# 2_66.net
KiCad netlist of a schematic drawn in EasyEDA Pro
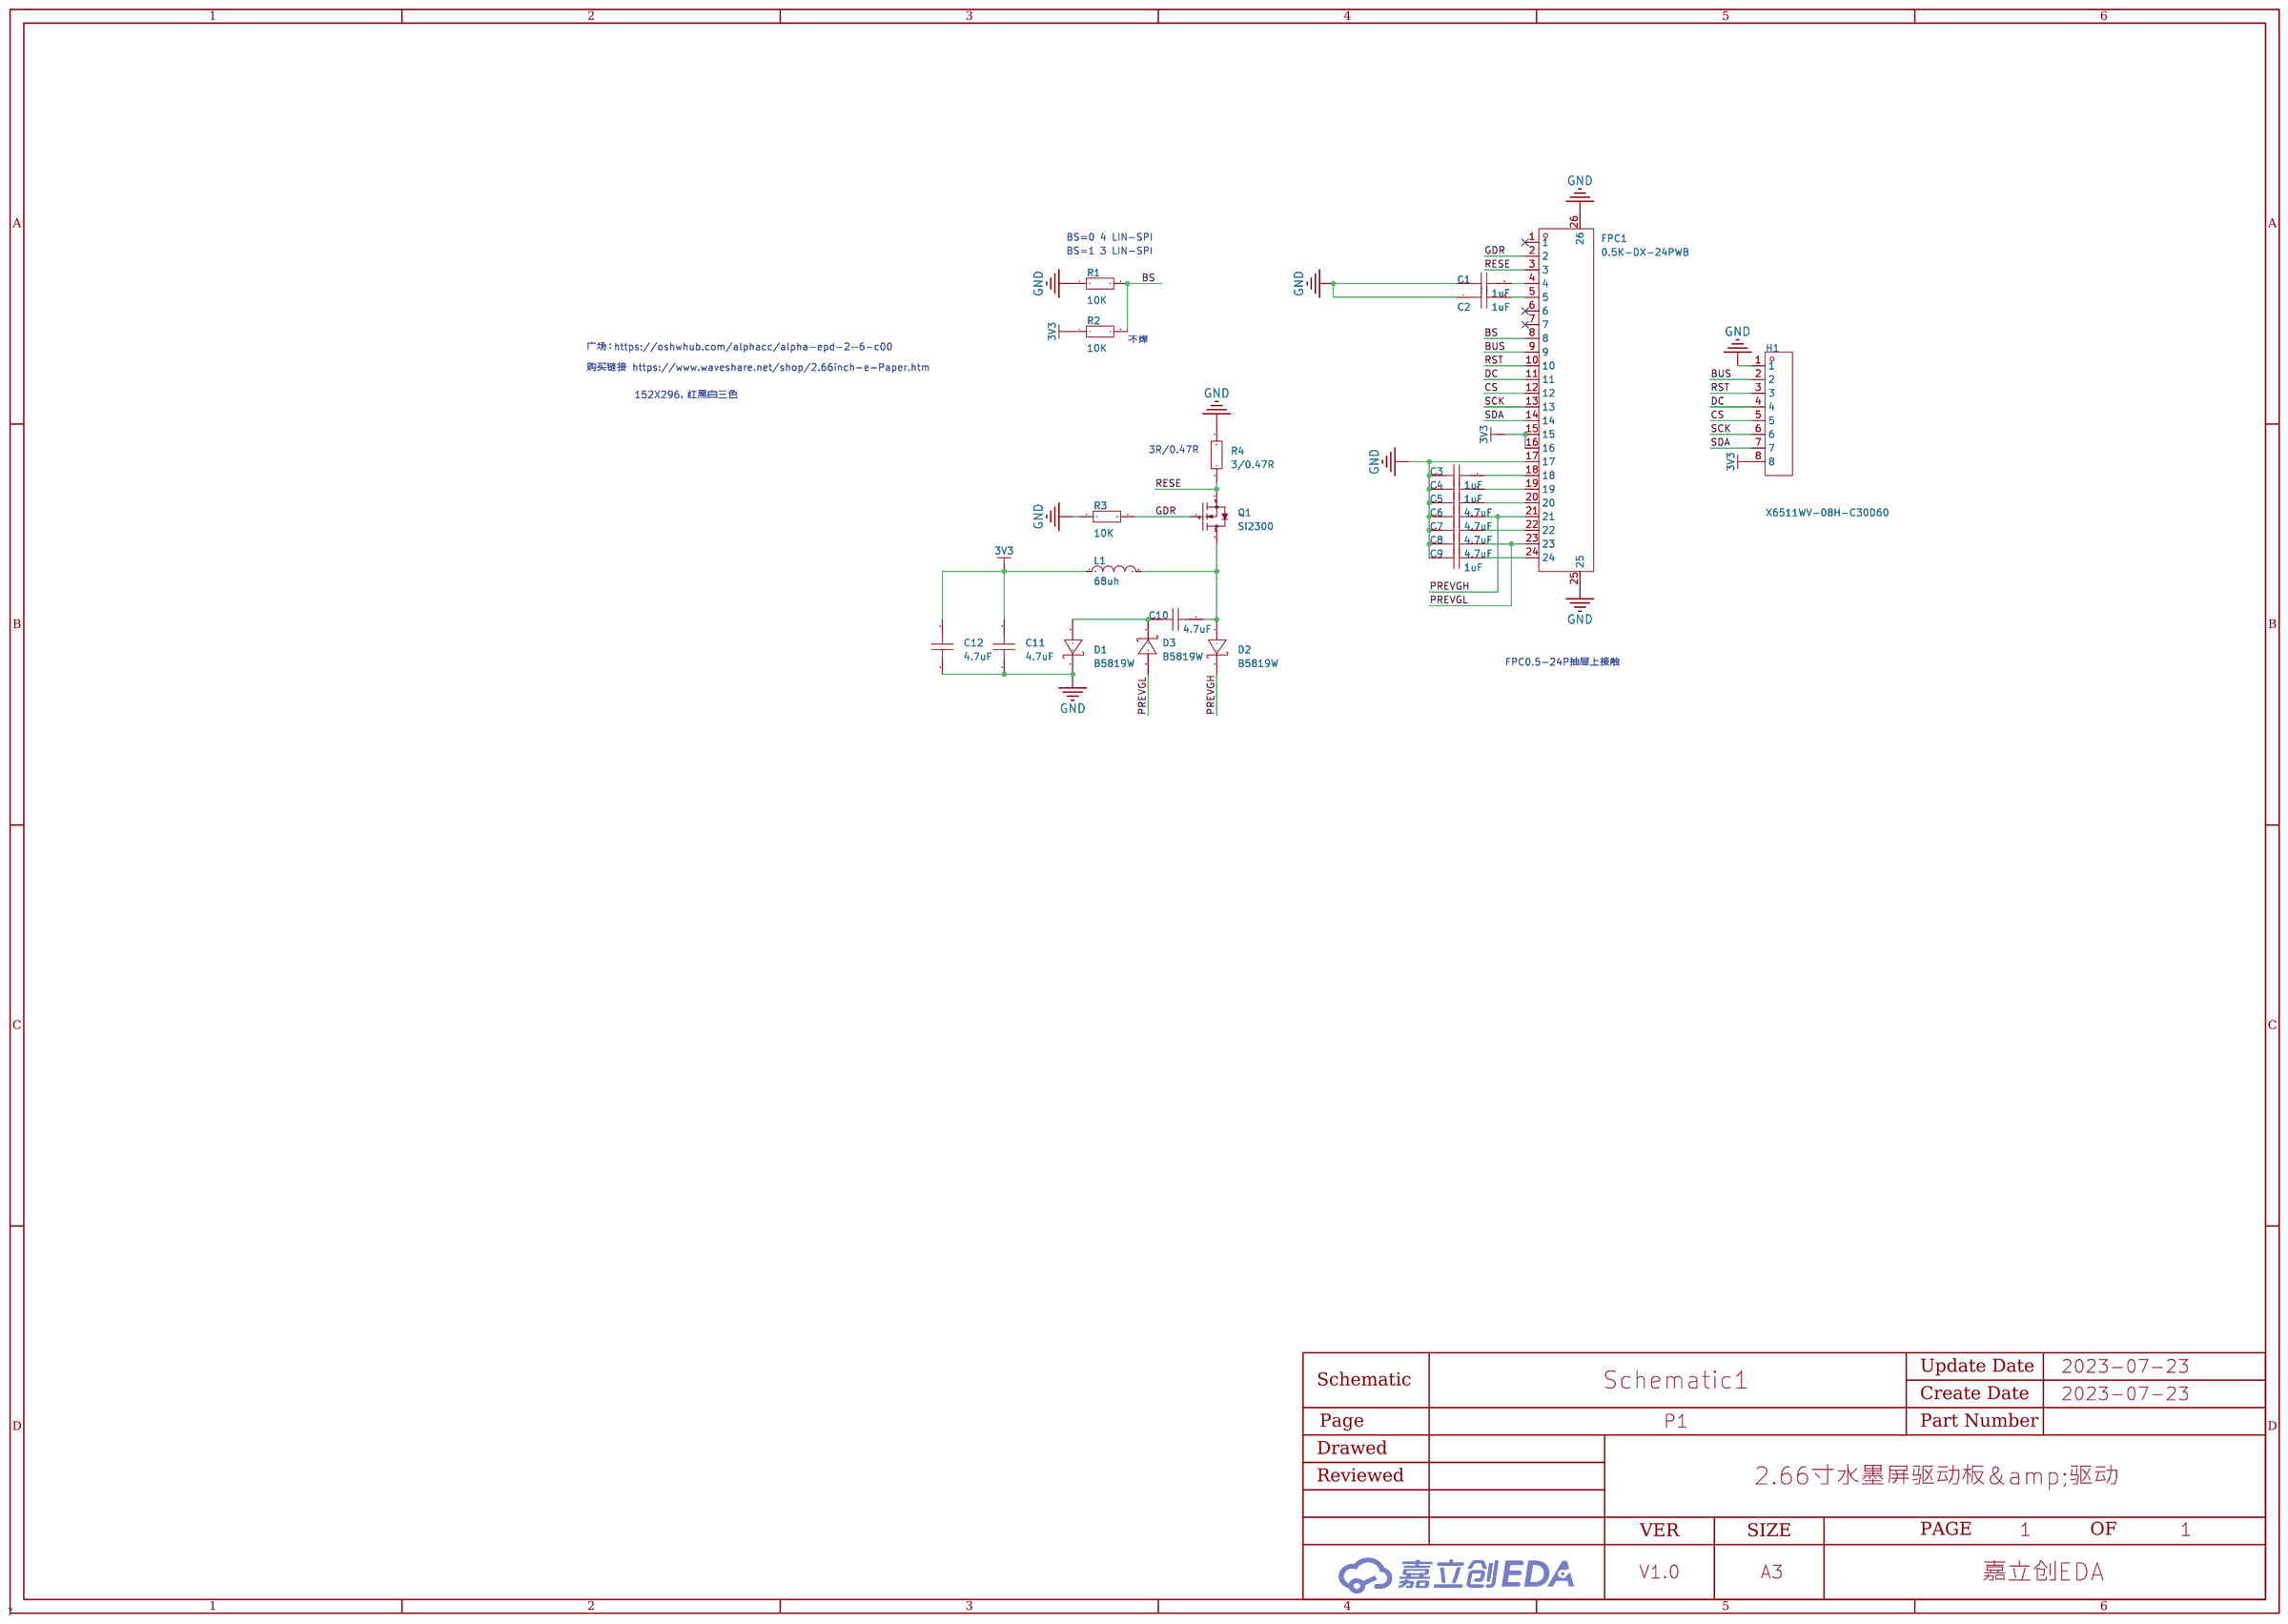
[diagram p0: schematic sheet]

(export (version "E")
  (design (tool "Eeschema 10.0.6"))
  (components
    (comp (ref "C1")
      (value "1uF")
      (footprint "easyedapro:C0603")
      (libsource (lib "easyedapro") (part "CapAcitance"))
    )
    (comp (ref "C2")
      (value "1uF")
      (footprint "easyedapro:C0603")
      (libsource (lib "easyedapro") (part "CapAcitance"))
    )
    (comp (ref "C3")
      (value "1uF")
      (footprint "easyedapro:C0603")
      (libsource (lib "easyedapro") (part "CapAcitance"))
    )
    (comp (ref "C4")
      (value "1uF")
      (footprint "easyedapro:C0603")
      (libsource (lib "easyedapro") (part "CapAcitance"))
    )
    (comp (ref "C5")
      (value "4.7uF")
      (footprint "easyedapro:C0603")
      (libsource (lib "easyedapro") (part "CapAcitance"))
    )
    (comp (ref "C6")
      (value "4.7uF")
      (footprint "easyedapro:C0603")
      (libsource (lib "easyedapro") (part "CapAcitance"))
    )
    (comp (ref "C7")
      (value "4.7uF")
      (footprint "easyedapro:C0603")
      (libsource (lib "easyedapro") (part "CapAcitance"))
    )
    (comp (ref "C8")
      (value "4.7uF")
      (footprint "easyedapro:C0603")
      (libsource (lib "easyedapro") (part "CapAcitance"))
    )
    (comp (ref "C9")
      (value "1uF")
      (footprint "easyedapro:C0603")
      (libsource (lib "easyedapro") (part "CapAcitance"))
    )
    (comp (ref "C10")
      (value "4.7uF")
      (footprint "easyedapro:C0603")
      (libsource (lib "easyedapro") (part "CapAcitance"))
    )
    (comp (ref "C11")
      (value "4.7uF")
      (footprint "easyedapro:C0603")
      (libsource (lib "easyedapro") (part "CapAcitance"))
    )
    (comp (ref "C12")
      (value "4.7uF")
      (footprint "easyedapro:C0603")
      (libsource (lib "easyedapro") (part "CapAcitance"))
    )
    (comp (ref "D1")
      (value "B5819W")
      (footprint "easyedapro:SOD-123_L2.8-W1.8-LS3.7-RD")
      (description "直流反向耐压(Vr):40V;平均整流电流(Io):1A;正向压降(Vf):600mV@1A;")
      (fields (field (name "Manufacturer") "MDD"))
      (libsource (lib "easyedapro") (part "B5819W"))
    )
    (comp (ref "D2")
      (value "B5819W")
      (footprint "easyedapro:SOD-123_L2.8-W1.8-LS3.7-RD")
      (description "直流反向耐压(Vr):40V;平均整流电流(Io):1A;正向压降(Vf):600mV@1A;")
      (fields (field (name "Manufacturer") "MDD"))
      (libsource (lib "easyedapro") (part "B5819W"))
    )
    (comp (ref "D3")
      (value "B5819W")
      (footprint "easyedapro:SOD-123_L2.8-W1.8-LS3.7-RD")
      (description "直流反向耐压(Vr):40V;平均整流电流(Io):1A;正向压降(Vf):600mV@1A;")
      (fields (field (name "Manufacturer") "MDD"))
      (libsource (lib "easyedapro") (part "B5819W"))
    )
    (comp (ref "FPC1")
      (value "0.5K-DX-24PWB")
      (footprint "easyedapro:FPC-SMD_24P-P0.50_HDGC_0.5K-DX-24PWBG")
      (description "FPC0.5间距2.0高掀盖式下接24P")
      (fields (field (name "Manufacturer") "HDGC(华德共创)"))
      (libsource (lib "easyedapro") (part "0.5K-DX-24PWB"))
    )
    (comp (ref "H1")
      (value "X6511WV-08H-C30D60")
      (footprint "easyedapro:HDR-TH_8P-P2.54-V-M")
      (fields (field (name "Manufacturer") "XKB Connectivity(中国星坤)"))
      (libsource (lib "easyedapro") (part "X6511WV-08H-C30D60"))
    )
    (comp (ref "L1")
      (value "68uh")
      (footprint "easyedapro:IND-SMD_L4.5-W4.0")
      (fields (field (name "Manufacturer") "DMBJ(振宝佳)"))
      (libsource (lib "easyedapro") (part "CD43-2R2M"))
    )
    (comp (ref "Q1")
      (value "SI2300")
      (footprint "easyedapro:SOT-23-3_L2.9-W1.3-P1.90-LS2.4-BR")
      (fields (field (name "Manufacturer") "Hottech(合科泰)"))
      (libsource (lib "easyedapro") (part "SI2300"))
    )
    (comp (ref "R1") (value "10K") (footprint "easyedapro:R0603") (libsource (lib "easyedapro") (part "电阻")))
    (comp (ref "R2") (value "10K") (footprint "easyedapro:R0603") (libsource (lib "easyedapro") (part "电阻")))
    (comp (ref "R3") (value "10K") (footprint "easyedapro:R0603") (libsource (lib "easyedapro") (part "电阻")))
    (comp (ref "R4")
      (value "3/0.47R")
      (footprint "easyedapro:R0603")
      (libsource (lib "easyedapro") (part "电阻"))
    )
  )
  (nets
    (net (code "1") (name "/BS") (class "Default")
      (node (ref "FPC1") (pin "8") (pinfunction "8_8") (pintype "input"))
      (node (ref "R1") (pin "2") (pinfunction "2_2") (pintype "input"))
      (node (ref "R2") (pin "2") (pinfunction "2_2") (pintype "input"))
    )
    (net (code "2") (name "/BUS") (class "Default")
      (node (ref "FPC1") (pin "9") (pinfunction "9_9") (pintype "input"))
      (node (ref "H1") (pin "2") (pinfunction "2_2") (pintype "input"))
    )
    (net (code "3") (name "/CS") (class "Default")
      (node (ref "FPC1") (pin "12") (pinfunction "12_12") (pintype "input"))
      (node (ref "H1") (pin "5") (pinfunction "5_5") (pintype "input"))
    )
    (net (code "4") (name "/DC") (class "Default")
      (node (ref "FPC1") (pin "11") (pinfunction "11_11") (pintype "input"))
      (node (ref "H1") (pin "4") (pinfunction "4_4") (pintype "input"))
    )
    (net (code "5") (name "/GDR") (class "Default")
      (node (ref "FPC1") (pin "2") (pinfunction "2_2") (pintype "input"))
      (node (ref "Q1") (pin "1") (pinfunction "G_1") (pintype "input"))
      (node (ref "R3") (pin "2") (pinfunction "2_2") (pintype "input"))
    )
    (net (code "6") (name "/PREVGH") (class "Default")
      (node (ref "C6") (pin "2") (pinfunction "2_2") (pintype "input"))
      (node (ref "D2") (pin "1") (pinfunction "K_1") (pintype "input"))
      (node (ref "FPC1") (pin "21") (pinfunction "21_21") (pintype "input"))
    )
    (net (code "7") (name "/PREVGL") (class "Default")
      (node (ref "C8") (pin "2") (pinfunction "2_2") (pintype "input"))
      (node (ref "D3") (pin "2") (pinfunction "A_2") (pintype "input"))
      (node (ref "FPC1") (pin "23") (pinfunction "23_23") (pintype "input"))
    )
    (net (code "8") (name "/RESE") (class "Default")
      (node (ref "FPC1") (pin "3") (pinfunction "3_3") (pintype "input"))
      (node (ref "Q1") (pin "2") (pinfunction "S_2") (pintype "input"))
      (node (ref "R4") (pin "1") (pinfunction "1_1") (pintype "input"))
    )
    (net (code "9") (name "/RST") (class "Default")
      (node (ref "FPC1") (pin "10") (pinfunction "10_10") (pintype "input"))
      (node (ref "H1") (pin "3") (pinfunction "3_3") (pintype "input"))
    )
    (net (code "10") (name "/SCK") (class "Default")
      (node (ref "FPC1") (pin "13") (pinfunction "13_13") (pintype "input"))
      (node (ref "H1") (pin "6") (pinfunction "6_6") (pintype "input"))
    )
    (net (code "11") (name "/SDA") (class "Default")
      (node (ref "FPC1") (pin "14") (pinfunction "14_14") (pintype "input"))
      (node (ref "H1") (pin "7") (pinfunction "7_7") (pintype "input"))
    )
    (net (code "12") (name "3V3") (class "Default")
      (node (ref "C11") (pin "2") (pinfunction "2_2") (pintype "input"))
      (node (ref "C12") (pin "2") (pinfunction "2_2") (pintype "input"))
      (node (ref "FPC1") (pin "15") (pinfunction "15_15") (pintype "input"))
      (node (ref "FPC1") (pin "16") (pinfunction "16_16") (pintype "input"))
      (node (ref "H1") (pin "8") (pinfunction "8_8") (pintype "input"))
      (node (ref "L1") (pin "1") (pinfunction "1_1") (pintype "input"))
      (node (ref "R2") (pin "1") (pinfunction "1_1") (pintype "input"))
    )
    (net (code "13") (name "GND") (class "Default")
      (node (ref "C1") (pin "1") (pinfunction "1_1") (pintype "input"))
      (node (ref "C11") (pin "1") (pinfunction "1_1") (pintype "input"))
      (node (ref "C12") (pin "1") (pinfunction "1_1") (pintype "input"))
      (node (ref "C2") (pin "1") (pinfunction "1_1") (pintype "input"))
      (node (ref "C3") (pin "1") (pinfunction "1_1") (pintype "input"))
      (node (ref "C4") (pin "1") (pinfunction "1_1") (pintype "input"))
      (node (ref "C5") (pin "1") (pinfunction "1_1") (pintype "input"))
      (node (ref "C6") (pin "1") (pinfunction "1_1") (pintype "input"))
      (node (ref "C7") (pin "1") (pinfunction "1_1") (pintype "input"))
      (node (ref "C8") (pin "1") (pinfunction "1_1") (pintype "input"))
      (node (ref "C9") (pin "1") (pinfunction "1_1") (pintype "input"))
      (node (ref "D1") (pin "1") (pinfunction "K_1") (pintype "input"))
      (node (ref "FPC1") (pin "17") (pinfunction "17_17") (pintype "input"))
      (node (ref "FPC1") (pin "25") (pinfunction "25_25") (pintype "input"))
      (node (ref "FPC1") (pin "26") (pinfunction "26_26") (pintype "input"))
      (node (ref "H1") (pin "1") (pinfunction "1_1") (pintype "input"))
      (node (ref "R1") (pin "1") (pinfunction "1_1") (pintype "input"))
      (node (ref "R3") (pin "1") (pinfunction "1_1") (pintype "input"))
      (node (ref "R4") (pin "2") (pinfunction "2_2") (pintype "input"))
    )
    (net (code "14") (name "Net-(C1-Pad2)") (class "Default")
      (node (ref "C1") (pin "2") (pinfunction "2_2") (pintype "input"))
      (node (ref "FPC1") (pin "4") (pinfunction "4_4") (pintype "input"))
    )
    (net (code "15") (name "Net-(C2-Pad2)") (class "Default")
      (node (ref "C2") (pin "2") (pinfunction "2_2") (pintype "input"))
      (node (ref "FPC1") (pin "5") (pinfunction "5_5") (pintype "input"))
    )
    (net (code "16") (name "Net-(C3-Pad2)") (class "Default")
      (node (ref "C3") (pin "2") (pinfunction "2_2") (pintype "input"))
      (node (ref "FPC1") (pin "18") (pinfunction "18_18") (pintype "input"))
    )
    (net (code "17") (name "Net-(C4-Pad2)") (class "Default")
      (node (ref "C4") (pin "2") (pinfunction "2_2") (pintype "input"))
      (node (ref "FPC1") (pin "19") (pinfunction "19_19") (pintype "input"))
    )
    (net (code "18") (name "Net-(C5-Pad2)") (class "Default")
      (node (ref "C5") (pin "2") (pinfunction "2_2") (pintype "input"))
      (node (ref "FPC1") (pin "20") (pinfunction "20_20") (pintype "input"))
    )
    (net (code "19") (name "Net-(C7-Pad2)") (class "Default")
      (node (ref "C7") (pin "2") (pinfunction "2_2") (pintype "input"))
      (node (ref "FPC1") (pin "22") (pinfunction "22_22") (pintype "input"))
    )
    (net (code "20") (name "Net-(C9-Pad2)") (class "Default")
      (node (ref "C9") (pin "2") (pinfunction "2_2") (pintype "input"))
      (node (ref "FPC1") (pin "24") (pinfunction "24_24") (pintype "input"))
    )
    (net (code "21") (name "Net-(D1-A)") (class "Default")
      (node (ref "C10") (pin "1") (pinfunction "1_1") (pintype "input"))
      (node (ref "D1") (pin "2") (pinfunction "A_2") (pintype "input"))
      (node (ref "D3") (pin "1") (pinfunction "K_1") (pintype "input"))
    )
    (net (code "22") (name "Net-(D2-A)") (class "Default")
      (node (ref "C10") (pin "2") (pinfunction "2_2") (pintype "input"))
      (node (ref "D2") (pin "2") (pinfunction "A_2") (pintype "input"))
      (node (ref "L1") (pin "2") (pinfunction "2_2") (pintype "input"))
      (node (ref "Q1") (pin "3") (pinfunction "D_3") (pintype "input"))
    )
    (net (code "23") (name "unconnected-(FPC1-Pad1)") (class "Default")
      (node (ref "FPC1") (pin "1") (pinfunction "1_1") (pintype "input+no_connect"))
    )
    (net (code "24") (name "unconnected-(FPC1-Pad6)") (class "Default")
      (node (ref "FPC1") (pin "6") (pinfunction "6_6") (pintype "input+no_connect"))
    )
    (net (code "25") (name "unconnected-(FPC1-Pad7)") (class "Default")
      (node (ref "FPC1") (pin "7") (pinfunction "7_7") (pintype "input+no_connect"))
    )
  )
)
